# SL-CA025-ESP07S_V1_0.net
KiCad netlist of a schematic drawn in Altium Designer
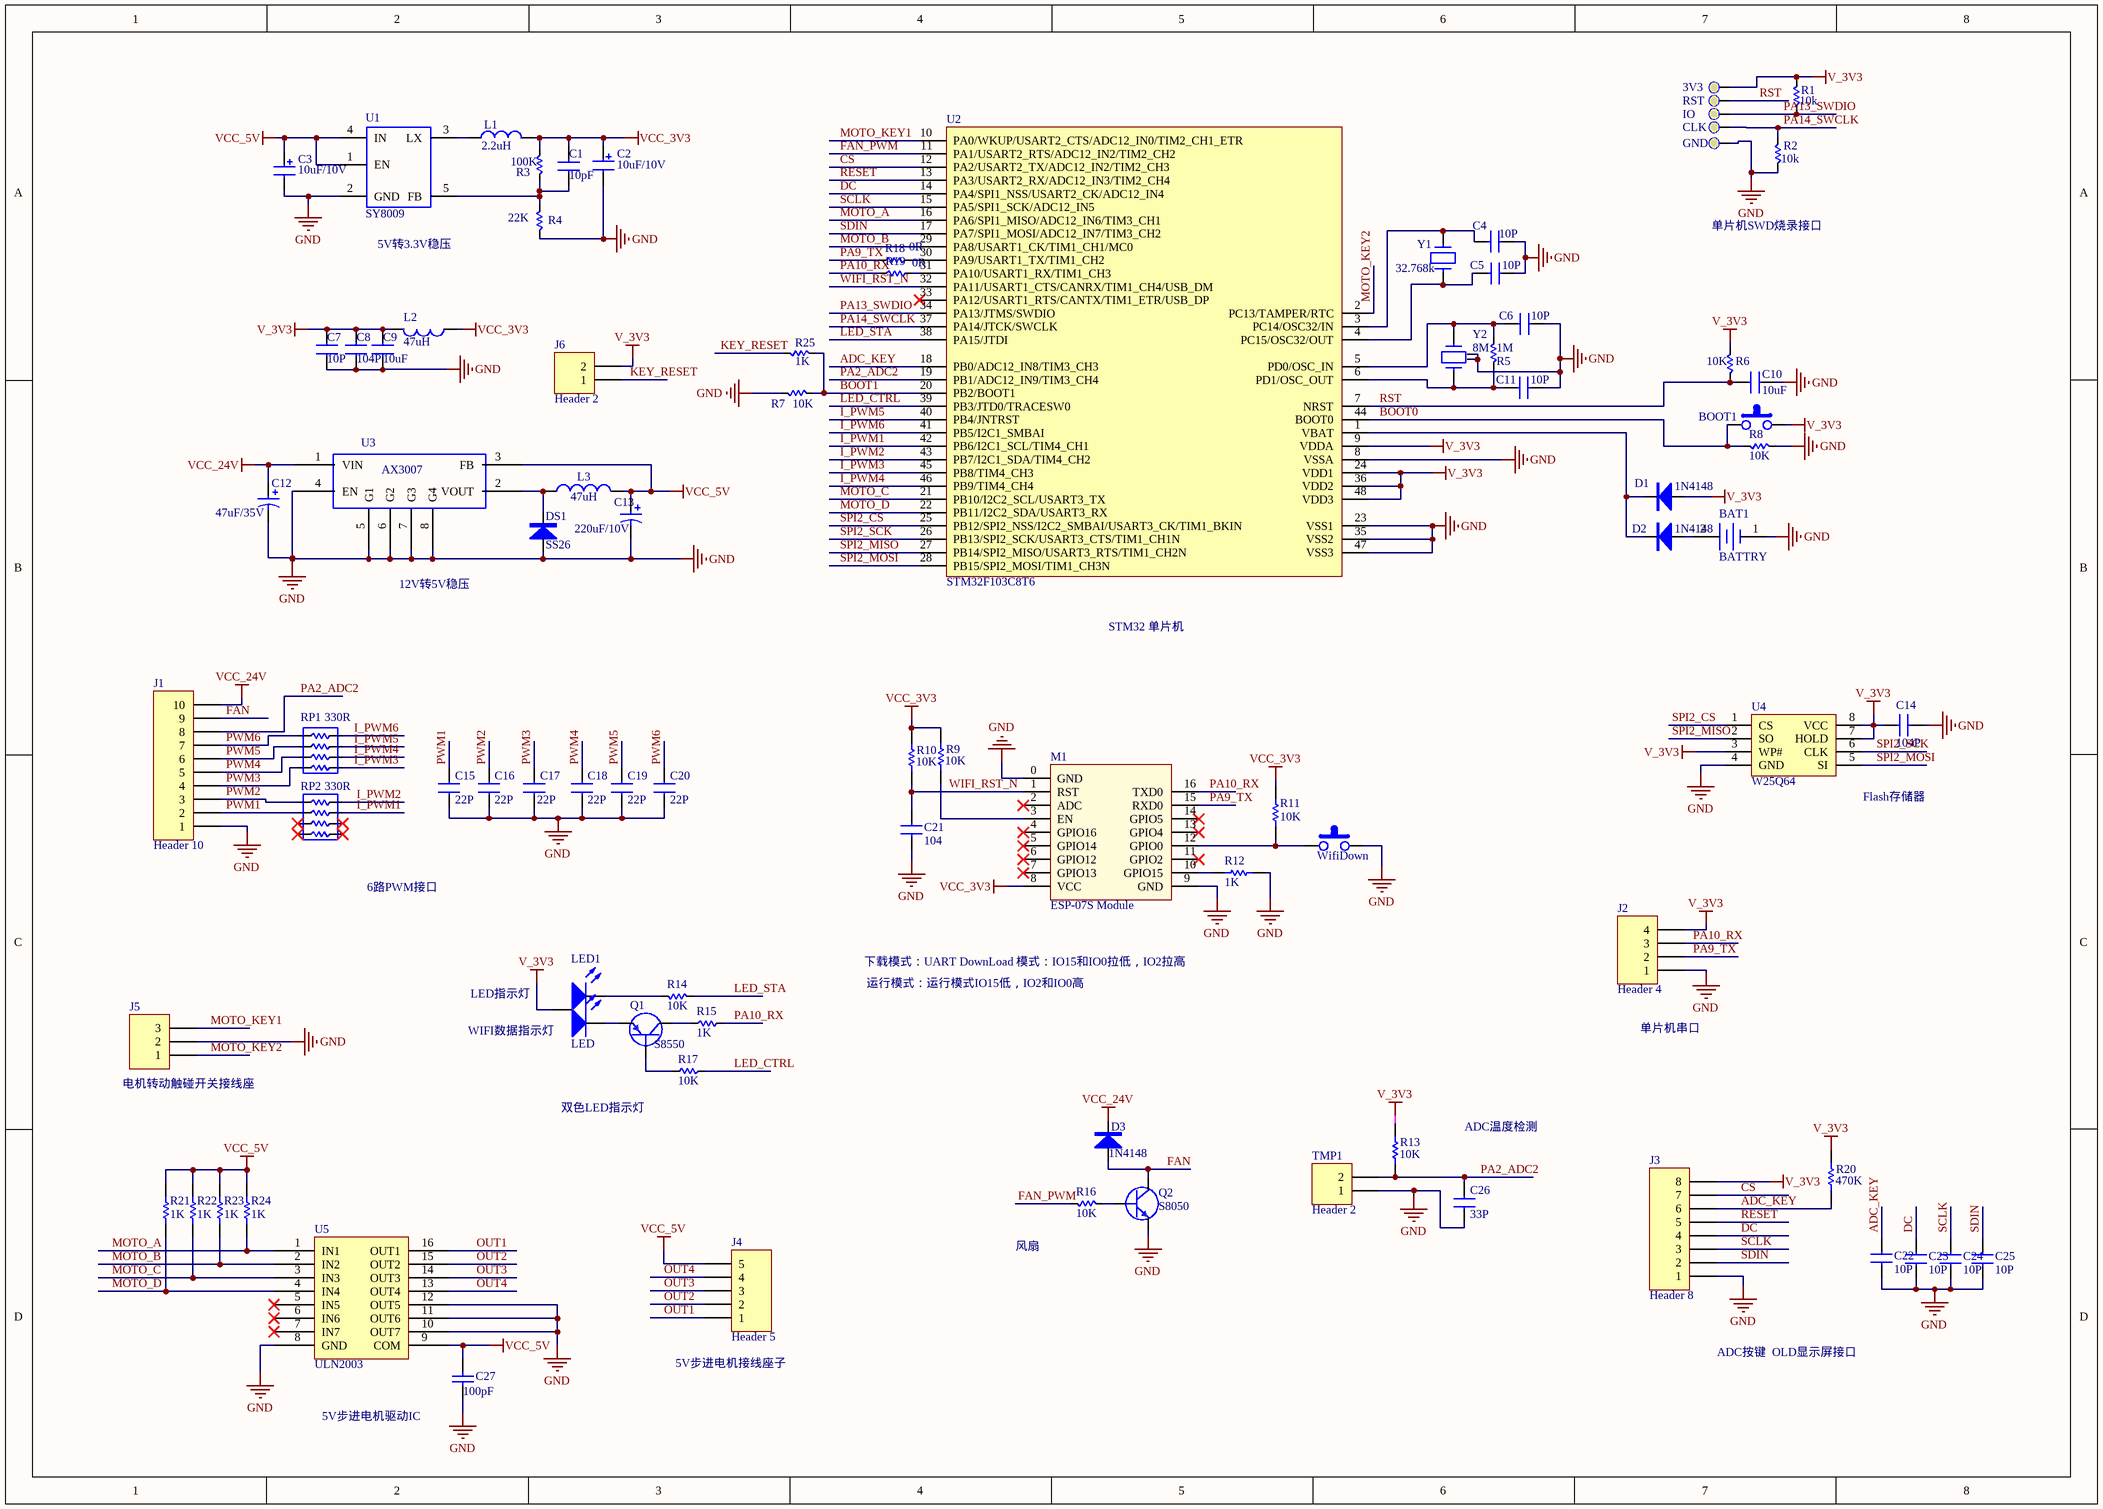
[diagram p0: SL-CA025-ESP07S_V1.0.SchDoc]

(export (version "E")
  (design (tool "Eeschema 10.0.6"))
  (components
    (comp (ref "3V3") (value "TP") (footprint "TP1") (libsource (lib "LED调光控制板") (part "TP1")))
    (comp (ref "BAT1") (value "BATTRY") (footprint "BAT_1220") (libsource (lib "LED调光控制板") (part "BATTRY")))
    (comp (ref "BOOT1") (value "SW") (footprint "SW_3X6") (libsource (lib "") (part "Button2_1")))
    (comp (ref "C1")
      (value "10pF")
      (footprint "C0603")
      (description "Capacitor")
      (libsource (lib "LED调光控制板") (part "CAP"))
    )
    (comp (ref "C2") (value "10uF/10V") (footprint "C0805") (libsource (lib "LED调光控制板") (part "CAP+")))
    (comp (ref "C3") (value "10uF/10V") (footprint "C0805") (libsource (lib "LED调光控制板") (part "CAP+")))
    (comp (ref "C4")
      (value "10P")
      (footprint "C0603")
      (description "Capacitor")
      (libsource (lib "LED调光控制板") (part "CAP"))
    )
    (comp (ref "C5")
      (value "10P")
      (footprint "C0603")
      (description "Capacitor")
      (libsource (lib "LED调光控制板") (part "CAP"))
    )
    (comp (ref "C6")
      (value "10P")
      (footprint "C0603")
      (description "Capacitor")
      (libsource (lib "LED调光控制板") (part "CAP"))
    )
    (comp (ref "C7")
      (value "10P")
      (footprint "C0603")
      (description "Capacitor")
      (libsource (lib "LED调光控制板") (part "CAP"))
    )
    (comp (ref "C8")
      (value "104P")
      (footprint "C0603")
      (description "Capacitor")
      (libsource (lib "LED调光控制板") (part "CAP"))
    )
    (comp (ref "C9")
      (value "10uF")
      (footprint "C0805")
      (description "Capacitor")
      (libsource (lib "LED调光控制板") (part "CAP"))
    )
    (comp (ref "C10")
      (value "10uF")
      (footprint "C0805")
      (description "Capacitor")
      (libsource (lib "LED调光控制板") (part "CAP"))
    )
    (comp (ref "C11")
      (value "10P")
      (footprint "C0603")
      (description "Capacitor")
      (libsource (lib "LED调光控制板") (part "CAP"))
    )
    (comp (ref "C12")
      (value "47uF/35V")
      (footprint "C_SMT63(5.9*6.6mm)")
      (description "Bi-Polar Capacitor")
      (libsource (lib "模拟器件") (part "CAP2"))
    )
    (comp (ref "C13")
      (value "220uF/10V")
      (footprint "C_SMT63(5.9*6.6mm)")
      (description "Bi-Polar Capacitor")
      (libsource (lib "模拟器件") (part "CAP2"))
    )
    (comp (ref "C14")
      (value "104P")
      (footprint "C0603")
      (description "Capacitor")
      (libsource (lib "LED调光控制板") (part "CAP"))
    )
    (comp (ref "C15")
      (value "22P")
      (footprint "C0603")
      (description "Capacitor")
      (libsource (lib "LED调光控制板") (part "CAP"))
    )
    (comp (ref "C16")
      (value "22P")
      (footprint "C0603")
      (description "Capacitor")
      (libsource (lib "LED调光控制板") (part "CAP"))
    )
    (comp (ref "C17")
      (value "22P")
      (footprint "C0603")
      (description "Capacitor")
      (libsource (lib "LED调光控制板") (part "CAP"))
    )
    (comp (ref "C18")
      (value "22P")
      (footprint "C0603")
      (description "Capacitor")
      (libsource (lib "LED调光控制板") (part "CAP"))
    )
    (comp (ref "C19")
      (value "22P")
      (footprint "C0603")
      (description "Capacitor")
      (libsource (lib "LED调光控制板") (part "CAP"))
    )
    (comp (ref "C20")
      (value "22P")
      (footprint "C0603")
      (description "Capacitor")
      (libsource (lib "LED调光控制板") (part "CAP"))
    )
    (comp (ref "C21")
      (value "104")
      (footprint "C0603")
      (description "Capacitor")
      (libsource (lib "LED调光控制板") (part "CAP"))
    )
    (comp (ref "C22")
      (value "10P")
      (footprint "C0603")
      (description "Capacitor")
      (libsource (lib "LED调光控制板") (part "CAP"))
    )
    (comp (ref "C23")
      (value "10P")
      (footprint "C0603")
      (description "Capacitor")
      (libsource (lib "LED调光控制板") (part "CAP"))
    )
    (comp (ref "C24")
      (value "10P")
      (footprint "C0603")
      (description "Capacitor")
      (libsource (lib "LED调光控制板") (part "CAP"))
    )
    (comp (ref "C25")
      (value "10P")
      (footprint "C0603")
      (description "Capacitor")
      (libsource (lib "LED调光控制板") (part "CAP"))
    )
    (comp (ref "C26")
      (value "33P")
      (footprint "C0603")
      (description "Capacitor")
      (libsource (lib "LED调光控制板") (part "CAP"))
    )
    (comp (ref "C27")
      (value "100pF")
      (footprint "C0603")
      (description "Capacitor")
      (fields (field (name "Comment") "Cap") (field (name "PUBLISHER") "Altium Limited"))
      (libsource (lib "Miscellaneous Devices") (part "Cap"))
    )
    (comp (ref "CLK") (value "TP") (footprint "TP1") (libsource (lib "LED调光控制板") (part "TP1")))
    (comp (ref "D1")
      (value "1N4148")
      (footprint "D0805")
      (description "DIODE")
      (libsource (lib "") (part "DIODE_2"))
    )
    (comp (ref "D2")
      (value "1N4148")
      (footprint "D0805")
      (description "DIODE")
      (libsource (lib "") (part "DIODE_1"))
    )
    (comp (ref "D3")
      (value "1N4148")
      (footprint "D0805")
      (description "DIODE")
      (libsource (lib "*") (part "DIODE"))
    )
    (comp (ref "DS1")
      (value "SS26")
      (footprint "SMA")
      (description "DIODE")
      (libsource (lib "") (part "DIODE_3"))
    )
    (comp (ref "GND") (value "TP") (footprint "TP1") (libsource (lib "LED调光控制板") (part "TP1")))
    (comp (ref "IO") (value "TP") (footprint "TP1") (libsource (lib "LED调光控制板") (part "TP1")))
    (comp (ref "J1")
      (value "Header 10")
      (footprint "CON10_1.5mm")
      (description "Header, 10-Pin, Right Angle")
      (fields (field (name "PUBLISHER") "Altium Limited"))
      (libsource (lib "Miscellaneous Connectors") (part "Header 10H"))
    )
    (comp (ref "J2")
      (value "Header 4")
      (footprint "SIP4A")
      (description "Header, 4-Pin")
      (fields (field (name "PUBLISHER") "Altium Limited"))
      (libsource (lib "Miscellaneous Connectors") (part "Header 4"))
    )
    (comp (ref "J3")
      (value "Header 8")
      (footprint "con8_1.5mm")
      (description "Header, 8-Pin")
      (fields (field (name "PUBLISHER") "Altium Limited"))
      (libsource (lib "Miscellaneous Connectors") (part "Header 8"))
    )
    (comp (ref "J4")
      (value "Header 5")
      (footprint "con5_1.5mm")
      (description "Header, 5-Pin")
      (fields (field (name "PUBLISHER") "Altium Limited"))
      (libsource (lib "Miscellaneous Connectors") (part "Header 5"))
    )
    (comp (ref "J5")
      (value "Header 3")
      (footprint "CON3_1.5mm")
      (description "Header, 3-Pin")
      (fields (field (name "PUBLISHER") "Altium Limited"))
      (libsource (lib "Miscellaneous Connectors") (part "Header 3"))
    )
    (comp (ref "J6")
      (value "Header 2")
      (footprint "CON2_1.5mm")
      (description "Header, 2-Pin")
      (fields (field (name "PUBLISHER") "Altium Limited"))
      (libsource (lib "Miscellaneous Connectors") (part "Header 2"))
    )
    (comp (ref "L1") (value "2.2uH") (footprint "L2520") (libsource (lib "LED调光控制板") (part "L")))
    (comp (ref "L2") (value "47uH") (footprint "L0805") (libsource (lib "LED调光控制板") (part "L")))
    (comp (ref "L3")
      (value "47uH")
      (footprint "L_SMRH_7.3x7.3")
      (description "Inductor")
      (libsource (lib "*") (part "INDUCTOR"))
    )
    (comp (ref "LED1")
      (value "LED")
      (footprint "LED_2K")
      (description "共阳极双色LED")
      (libsource (lib "MyShcLib") (part "LED_2K"))
    )
    (comp (ref "M1")
      (value "ESP-07S Module")
      (footprint "ESP-07S Module")
      (libsource (lib "ESP-07S Module") (part "ESP-07S Module"))
    )
    (comp (ref "Q1") (value "S8550") (footprint "SOT23-3") (libsource (lib "MyShcLib") (part "PNP")))
    (comp (ref "Q2") (value "S8050") (footprint "SOT23-3") (libsource (lib "LED调光控制板") (part "PNP2")))
    (comp (ref "R1") (value "10k") (footprint "R0603") (libsource (lib "LED调光控制板") (part "RES")))
    (comp (ref "R2") (value "10k") (footprint "R0603") (libsource (lib "LED调光控制板") (part "RES")))
    (comp (ref "R3") (value "100K") (footprint "R0603") (libsource (lib "LED调光控制板") (part "RES")))
    (comp (ref "R4") (value "22K") (footprint "R0603") (libsource (lib "LED调光控制板") (part "RES")))
    (comp (ref "R5") (value "1M") (footprint "R0603") (libsource (lib "LED调光控制板") (part "RES")))
    (comp (ref "R6") (value "10K") (footprint "R0603") (libsource (lib "LED调光控制板") (part "RES")))
    (comp (ref "R7") (value "10K") (footprint "R0603") (libsource (lib "LED调光控制板") (part "RES")))
    (comp (ref "R8") (value "10K") (footprint "R0603") (libsource (lib "LED调光控制板") (part "RES")))
    (comp (ref "R9")
      (value "10K")
      (footprint "R0603")
      (description "Resistor")
      (fields (field (name "PUBLISHER") "Altium Limited"))
      (libsource (lib "Miscellaneous Devices") (part "Res1"))
    )
    (comp (ref "R10")
      (value "10K")
      (footprint "R0603")
      (description "Resistor")
      (fields (field (name "PUBLISHER") "Altium Limited"))
      (libsource (lib "Miscellaneous Devices") (part "Res1"))
    )
    (comp (ref "R11")
      (value "10K")
      (footprint "R0603")
      (description "Resistor")
      (fields (field (name "PUBLISHER") "Altium Limited"))
      (libsource (lib "Miscellaneous Devices") (part "Res1"))
    )
    (comp (ref "R12")
      (value "1K")
      (footprint "R0603")
      (description "Resistor")
      (fields (field (name "PUBLISHER") "Altium Limited"))
      (libsource (lib "Miscellaneous Devices") (part "Res1"))
    )
    (comp (ref "R13")
      (value "10K")
      (footprint "R0603")
      (description "Resistor")
      (fields (field (name "PUBLISHER") "Altium Limited"))
      (libsource (lib "Miscellaneous Devices") (part "Res1"))
    )
    (comp (ref "R14") (value "10K") (footprint "R0603") (libsource (lib "LED调光控制板") (part "RES")))
    (comp (ref "R15") (value "1K") (footprint "R0603") (libsource (lib "LED调光控制板") (part "RES")))
    (comp (ref "R16") (value "10K") (footprint "R0603") (libsource (lib "LED调光控制板") (part "RES")))
    (comp (ref "R17") (value "10K") (footprint "R0603") (libsource (lib "LED调光控制板") (part "RES")))
    (comp (ref "R18") (value "0R") (footprint "R0603") (libsource (lib "LED调光控制板") (part "RES")))
    (comp (ref "R19") (value "0R") (footprint "R0603") (libsource (lib "LED调光控制板") (part "RES")))
    (comp (ref "R20")
      (value "470K")
      (footprint "R0603")
      (description "Resistor")
      (fields (field (name "PUBLISHER") "Altium Limited"))
      (libsource (lib "Miscellaneous Devices") (part "Res1"))
    )
    (comp (ref "R21")
      (value "1K")
      (footprint "R0603")
      (description "Resistor")
      (fields (field (name "Comment") "Res1") (field (name "PUBLISHER") "Altium Limited"))
      (libsource (lib "Miscellaneous Devices") (part "Res1"))
    )
    (comp (ref "R22")
      (value "1K")
      (footprint "R0603")
      (description "Resistor")
      (fields (field (name "Comment") "Res1") (field (name "PUBLISHER") "Altium Limited"))
      (libsource (lib "Miscellaneous Devices") (part "Res1"))
    )
    (comp (ref "R23")
      (value "1K")
      (footprint "R0603")
      (description "Resistor")
      (fields (field (name "Comment") "Res1") (field (name "PUBLISHER") "Altium Limited"))
      (libsource (lib "Miscellaneous Devices") (part "Res1"))
    )
    (comp (ref "R24")
      (value "1K")
      (footprint "R0603")
      (description "Resistor")
      (fields (field (name "Comment") "Res1") (field (name "PUBLISHER") "Altium Limited"))
      (libsource (lib "Miscellaneous Devices") (part "Res1"))
    )
    (comp (ref "R25") (value "1K") (footprint "R0603") (libsource (lib "LED调光控制板") (part "RES")))
    (comp (ref "RP1") (value "330R") (footprint "RP4_0603") (libsource (lib "LED调光控制板") (part "RES_PACK4")))
    (comp (ref "RP2") (value "330R") (footprint "RP4_0603") (libsource (lib "LED调光控制板") (part "RES_PACK4")))
    (comp (ref "RST") (value "TP") (footprint "TP1") (libsource (lib "LED调光控制板") (part "TP1")))
    (comp (ref "TMP1")
      (value "Header 2")
      (footprint "CON2_1.5mm")
      (description "Header, 2-Pin")
      (fields (field (name "PUBLISHER") "Altium Limited"))
      (libsource (lib "Miscellaneous Connectors") (part "Header 2"))
    )
    (comp (ref "U1") (value "SY8009") (footprint "SOT23-5") (libsource (lib "LED调光控制板") (part "SY8009")))
    (comp (ref "U2")
      (value "STM32F103C8T6")
      (footprint "LQFP48_9.2x9.2mm")
      (libsource (lib "LED调光控制板") (part "STM32F103C8T6"))
    )
    (comp (ref "U3") (value "AX3007") (footprint "SOP8_N") (libsource (lib "LED调光控制板") (part "AX3007")))
    (comp (ref "U4") (value "W25Q64") (footprint "SOIC8") (libsource (lib "LED调光控制板") (part "W25Q64")))
    (comp (ref "U5")
      (value "ULN2003")
      (footprint "SOP16")
      (description "电机驱动IC")
      (libsource (lib "ULN2003") (part "ULN2003"))
    )
    (comp (ref "WifiDown") (value "SW") (footprint "SW_3X6") (libsource (lib "LED调光控制板") (part "Button2")))
    (comp (ref "Y1") (value "32.768k") (footprint "XALT_3215") (libsource (lib "LED调光控制板") (part "CRYSTAL")))
    (comp (ref "Y2") (value "8M") (footprint "XALT_5032_4P") (libsource (lib "LED调光控制板") (part "Crystal_4p")))
  )
  (nets
    (net (code "1") (name "/ADC_KEY") (class "Default")
      (node (ref "C22") (pin "2") (pinfunction "2_2") (pintype "passive"))
      (node (ref "J3") (pin "6") (pinfunction "6_6") (pintype "passive"))
      (node (ref "R20") (pin "2") (pinfunction "2_2") (pintype "passive"))
      (node (ref "U2") (pin "18") (pinfunction "PB0/ADC12_IN8/TIM3_CH3_18") (pintype "passive"))
    )
    (net (code "2") (name "/BOOT0") (class "Default")
      (node (ref "BOOT1") (pin "1") (pinfunction "1_1") (pintype "passive"))
      (node (ref "R8") (pin "1") (pintype "passive"))
      (node (ref "U2") (pin "44") (pinfunction "BOOT0_44") (pintype "passive"))
    )
    (net (code "3") (name "/BOOT1") (class "Default")
      (node (ref "R25") (pin "1") (pintype "passive"))
      (node (ref "R7") (pin "1") (pintype "passive"))
      (node (ref "U2") (pin "20") (pinfunction "PB2/BOOT1_20") (pintype "passive"))
    )
    (net (code "4") (name "/CS") (class "Default")
      (node (ref "J3") (pin "7") (pinfunction "7_7") (pintype "passive"))
      (node (ref "U2") (pin "12") (pinfunction "PA2/USART2_TX/ADC12_IN2/TIM2_CH3_12") (pintype "passive"))
    )
    (net (code "5") (name "/DC") (class "Default")
      (node (ref "C23") (pin "2") (pinfunction "2_2") (pintype "passive"))
      (node (ref "J3") (pin "4") (pinfunction "4_4") (pintype "passive"))
      (node (ref "U2") (pin "14") (pinfunction "PA4/SPI1_NSS/USART2_CK/ADC12_IN4_14") (pintype "passive"))
    )
    (net (code "6") (name "/FAN") (class "Default")
      (node (ref "D3") (pin "1") (pinfunction "1_1") (pintype "passive"))
      (node (ref "J1") (pin "9") (pinfunction "9_9") (pintype "passive"))
      (node (ref "Q2") (pin "3") (pinfunction "E_3") (pintype "passive"))
    )
    (net (code "7") (name "/FAN_PWM") (class "Default")
      (node (ref "R16") (pin "1") (pintype "passive"))
      (node (ref "U2") (pin "11") (pinfunction "PA1/USART2_RTS/ADC12_IN2/TIM2_CH2_11") (pintype "passive"))
    )
    (net (code "8") (name "/I_PWM1") (class "Default")
      (node (ref "RP2") (pin "6") (pintype "passive"))
      (node (ref "U2") (pin "42") (pinfunction "PB6/I2C1_SCL/TIM4_CH1_42") (pintype "passive"))
    )
    (net (code "9") (name "/I_PWM2") (class "Default")
      (node (ref "RP2") (pin "5") (pintype "passive"))
      (node (ref "U2") (pin "43") (pinfunction "PB7/I2C1_SDA/TIM4_CH2_43") (pintype "passive"))
    )
    (net (code "10") (name "/I_PWM3") (class "Default")
      (node (ref "RP1") (pin "8") (pintype "passive"))
      (node (ref "U2") (pin "45") (pinfunction "PB8/TIM4_CH3_45") (pintype "passive"))
    )
    (net (code "11") (name "/I_PWM4") (class "Default")
      (node (ref "RP1") (pin "7") (pintype "passive"))
      (node (ref "U2") (pin "46") (pinfunction "PB9/TIM4_CH4_46") (pintype "passive"))
    )
    (net (code "12") (name "/I_PWM5") (class "Default")
      (node (ref "RP1") (pin "6") (pintype "passive"))
      (node (ref "U2") (pin "40") (pinfunction "PB4/JNTRST_40") (pintype "passive"))
    )
    (net (code "13") (name "/I_PWM6") (class "Default")
      (node (ref "RP1") (pin "5") (pintype "passive"))
      (node (ref "U2") (pin "41") (pinfunction "PB5/I2C1_SMBAI_41") (pintype "passive"))
    )
    (net (code "14") (name "/KEY_RESET") (class "Default")
      (node (ref "J6") (pin "1") (pinfunction "1_1") (pintype "passive"))
      (node (ref "R25") (pin "2") (pintype "passive"))
    )
    (net (code "15") (name "/LED_CTRL") (class "Default")
      (node (ref "R17") (pin "2") (pintype "passive"))
      (node (ref "U2") (pin "39") (pinfunction "PB3/JTD0/TRACESW0_39") (pintype "passive"))
    )
    (net (code "16") (name "/LED_STA") (class "Default")
      (node (ref "R14") (pin "1") (pintype "passive"))
      (node (ref "U2") (pin "38") (pinfunction "PA15/JTDI_38") (pintype "passive"))
    )
    (net (code "17") (name "/MOTO_A") (class "Default")
      (node (ref "R24") (pin "1") (pinfunction "1_1") (pintype "passive"))
      (node (ref "U2") (pin "16") (pinfunction "PA6/SPI1_MISO/ADC12_IN6/TIM3_CH1_16") (pintype "passive"))
      (node (ref "U5") (pin "1") (pinfunction "IN1_1") (pintype "passive"))
    )
    (net (code "18") (name "/MOTO_B") (class "Default")
      (node (ref "R23") (pin "1") (pinfunction "1_1") (pintype "passive"))
      (node (ref "U2") (pin "29") (pinfunction "PA8/USART1_CK/TIM1_CH1/MC0_29") (pintype "passive"))
      (node (ref "U5") (pin "2") (pinfunction "IN2_2") (pintype "passive"))
    )
    (net (code "19") (name "/MOTO_C") (class "Default")
      (node (ref "R22") (pin "1") (pinfunction "1_1") (pintype "passive"))
      (node (ref "U2") (pin "21") (pinfunction "PB10/I2C2_SCL/USART3_TX_21") (pintype "passive"))
      (node (ref "U5") (pin "3") (pinfunction "IN3_3") (pintype "passive"))
    )
    (net (code "20") (name "/MOTO_D") (class "Default")
      (node (ref "R21") (pin "1") (pinfunction "1_1") (pintype "passive"))
      (node (ref "U2") (pin "22") (pinfunction "PB11/I2C2_SDA/USART3_RX_22") (pintype "passive"))
      (node (ref "U5") (pin "4") (pinfunction "IN4_4") (pintype "passive"))
    )
    (net (code "21") (name "/MOTO_KEY1") (class "Default")
      (node (ref "J5") (pin "3") (pinfunction "3_3") (pintype "passive"))
      (node (ref "U2") (pin "10") (pinfunction "PA0/WKUP/USART2_CTS/ADC12_IN0/TIM2_CH1_ETR_10") (pintype "passive"))
    )
    (net (code "22") (name "/MOTO_KEY2") (class "Default")
      (node (ref "J5") (pin "1") (pinfunction "1_1") (pintype "passive"))
      (node (ref "U2") (pin "2") (pinfunction "PC13/TAMPER/RTC_2") (pintype "passive"))
    )
    (net (code "23") (name "/OUT1") (class "Default")
      (node (ref "J4") (pin "1") (pinfunction "1_1") (pintype "passive"))
      (node (ref "U5") (pin "16") (pinfunction "OUT1_16") (pintype "passive"))
    )
    (net (code "24") (name "/OUT2") (class "Default")
      (node (ref "J4") (pin "2") (pinfunction "2_2") (pintype "passive"))
      (node (ref "U5") (pin "15") (pinfunction "OUT2_15") (pintype "passive"))
    )
    (net (code "25") (name "/OUT3") (class "Default")
      (node (ref "J4") (pin "3") (pinfunction "3_3") (pintype "passive"))
      (node (ref "U5") (pin "14") (pinfunction "OUT3_14") (pintype "passive"))
    )
    (net (code "26") (name "/OUT4") (class "Default")
      (node (ref "J4") (pin "4") (pinfunction "4_4") (pintype "passive"))
      (node (ref "U5") (pin "13") (pinfunction "OUT4_13") (pintype "passive"))
    )
    (net (code "27") (name "/PA2_ADC2") (class "Default")
      (node (ref "C26") (pin "2") (pinfunction "2_2") (pintype "passive"))
      (node (ref "J1") (pin "8") (pinfunction "8_8") (pintype "passive"))
      (node (ref "R13") (pin "2") (pinfunction "2_2") (pintype "passive"))
      (node (ref "TMP1") (pin "2") (pinfunction "2_2") (pintype "passive"))
      (node (ref "U2") (pin "19") (pinfunction "PB1/ADC12_IN9/TIM3_CH4_19") (pintype "passive"))
    )
    (net (code "28") (name "/PA9_TX") (class "Default")
      (node (ref "J2") (pin "2") (pinfunction "2_2") (pintype "passive"))
      (node (ref "M1") (pin "15") (pinfunction "RXD0_15") (pintype "passive"))
      (node (ref "R18") (pin "1") (pintype "passive"))
    )
    (net (code "29") (name "/PA10_RX") (class "Default")
      (node (ref "J2") (pin "3") (pinfunction "3_3") (pintype "passive"))
      (node (ref "M1") (pin "16") (pinfunction "TXD0_16") (pintype "passive"))
      (node (ref "R15") (pin "1") (pintype "passive"))
      (node (ref "R19") (pin "1") (pintype "passive"))
    )
    (net (code "30") (name "/PA13_SWDIO") (class "Default")
      (node (ref "IO") (pin "1") (pinfunction "1_1") (pintype "passive"))
      (node (ref "R1") (pin "1") (pintype "passive"))
      (node (ref "U2") (pin "34") (pinfunction "PA13/JTMS/SWDIO_34") (pintype "passive"))
    )
    (net (code "31") (name "/PA14_SWCLK") (class "Default")
      (node (ref "CLK") (pin "1") (pinfunction "1_1") (pintype "passive"))
      (node (ref "R2") (pin "2") (pintype "passive"))
      (node (ref "U2") (pin "37") (pinfunction "PA14/JTCK/SWCLK_37") (pintype "passive"))
    )
    (net (code "32") (name "/PWM1") (class "Default")
      (node (ref "C15") (pin "2") (pinfunction "2_2") (pintype "passive"))
      (node (ref "J1") (pin "2") (pinfunction "2_2") (pintype "passive"))
      (node (ref "RP2") (pin "3") (pintype "passive"))
    )
    (net (code "33") (name "/PWM2") (class "Default")
      (node (ref "C16") (pin "2") (pinfunction "2_2") (pintype "passive"))
      (node (ref "J1") (pin "3") (pinfunction "3_3") (pintype "passive"))
      (node (ref "RP2") (pin "4") (pintype "passive"))
    )
    (net (code "34") (name "/PWM3") (class "Default")
      (node (ref "C17") (pin "2") (pinfunction "2_2") (pintype "passive"))
      (node (ref "J1") (pin "4") (pinfunction "4_4") (pintype "passive"))
      (node (ref "RP1") (pin "1") (pintype "passive"))
    )
    (net (code "35") (name "/PWM4") (class "Default")
      (node (ref "C18") (pin "2") (pinfunction "2_2") (pintype "passive"))
      (node (ref "J1") (pin "5") (pinfunction "5_5") (pintype "passive"))
      (node (ref "RP1") (pin "2") (pintype "passive"))
    )
    (net (code "36") (name "/PWM5") (class "Default")
      (node (ref "C19") (pin "2") (pinfunction "2_2") (pintype "passive"))
      (node (ref "J1") (pin "6") (pinfunction "6_6") (pintype "passive"))
      (node (ref "RP1") (pin "3") (pintype "passive"))
    )
    (net (code "37") (name "/PWM6") (class "Default")
      (node (ref "C20") (pin "2") (pinfunction "2_2") (pintype "passive"))
      (node (ref "J1") (pin "7") (pinfunction "7_7") (pintype "passive"))
      (node (ref "RP1") (pin "4") (pintype "passive"))
    )
    (net (code "38") (name "/RESET") (class "Default")
      (node (ref "J3") (pin "5") (pinfunction "5_5") (pintype "passive"))
      (node (ref "U2") (pin "13") (pinfunction "PA3/USART2_RX/ADC12_IN3/TIM2_CH4_13") (pintype "passive"))
    )
    (net (code "39") (name "/RST") (class "Default")
      (node (ref "C10") (pin "1") (pinfunction "1_1") (pintype "passive"))
      (node (ref "R6") (pin "1") (pintype "passive"))
      (node (ref "RST") (pin "1") (pinfunction "1_1") (pintype "passive"))
      (node (ref "U2") (pin "7") (pinfunction "NRST_7") (pintype "passive"))
    )
    (net (code "40") (name "/SCLK") (class "Default")
      (node (ref "C24") (pin "2") (pinfunction "2_2") (pintype "passive"))
      (node (ref "J3") (pin "3") (pinfunction "3_3") (pintype "passive"))
      (node (ref "U2") (pin "15") (pinfunction "PA5/SPI1_SCK/ADC12_IN5_15") (pintype "passive"))
    )
    (net (code "41") (name "/SDIN") (class "Default")
      (node (ref "C25") (pin "2") (pinfunction "2_2") (pintype "passive"))
      (node (ref "J3") (pin "2") (pinfunction "2_2") (pintype "passive"))
      (node (ref "U2") (pin "17") (pinfunction "PA7/SPI1_MOSI/ADC12_IN7/TIM3_CH2_17") (pintype "passive"))
    )
    (net (code "42") (name "/SPI2_CS") (class "Default")
      (node (ref "U2") (pin "25") (pinfunction "PB12/SPI2_NSS/I2C2_SMBAI/USART3_CK/TIM1_BKIN_25") (pintype "passive"))
      (node (ref "U4") (pin "1") (pinfunction "CS_1") (pintype "passive"))
    )
    (net (code "43") (name "/SPI2_MISO") (class "Default")
      (node (ref "U2") (pin "27") (pinfunction "PB14/SPI2_MISO/USART3_RTS/TIM1_CH2N_27") (pintype "passive"))
      (node (ref "U4") (pin "2") (pinfunction "SO_2") (pintype "passive"))
    )
    (net (code "44") (name "/SPI2_MOSI") (class "Default")
      (node (ref "U2") (pin "28") (pinfunction "PB15/SPI2_MOSI/TIM1_CH3N_28") (pintype "passive"))
      (node (ref "U4") (pin "5") (pinfunction "SI_5") (pintype "passive"))
    )
    (net (code "45") (name "/SPI2_SCK") (class "Default")
      (node (ref "U2") (pin "26") (pinfunction "PB13/SPI2_SCK/USART3_CTS/TIM1_CH1N_26") (pintype "passive"))
      (node (ref "U4") (pin "6") (pinfunction "CLK_6") (pintype "passive"))
    )
    (net (code "46") (name "/WIFI_RST_N") (class "Default")
      (node (ref "C21") (pin "1") (pinfunction "1_1") (pintype "passive"))
      (node (ref "M1") (pin "1") (pinfunction "RST_1") (pintype "passive"))
      (node (ref "R10") (pin "2") (pinfunction "2_2") (pintype "passive"))
      (node (ref "U2") (pin "32") (pinfunction "PA11/USART1_CTS/CANRX/TIM1_CH4/USB_DM_32") (pintype "passive"))
    )
    (net (code "47") (name "GND") (class "Default")
      (node (ref "BAT1") (pin "1") (pintype "passive"))
      (node (ref "C10") (pin "2") (pinfunction "2_2") (pintype "passive"))
      (node (ref "C11") (pin "2") (pinfunction "2_2") (pintype "passive"))
      (node (ref "C12") (pin "2") (pinfunction "2_2") (pintype "passive"))
      (node (ref "C13") (pin "2") (pinfunction "2_2") (pintype "passive"))
      (node (ref "C14") (pin "2") (pinfunction "2_2") (pintype "passive"))
      (node (ref "C15") (pin "1") (pinfunction "1_1") (pintype "passive"))
      (node (ref "C16") (pin "1") (pinfunction "1_1") (pintype "passive"))
      (node (ref "C17") (pin "1") (pinfunction "1_1") (pintype "passive"))
      (node (ref "C18") (pin "1") (pinfunction "1_1") (pintype "passive"))
      (node (ref "C19") (pin "1") (pinfunction "1_1") (pintype "passive"))
      (node (ref "C2") (pin "2") (pinfunction "2_2") (pintype "passive"))
      (node (ref "C20") (pin "1") (pinfunction "1_1") (pintype "passive"))
      (node (ref "C21") (pin "2") (pinfunction "2_2") (pintype "passive"))
      (node (ref "C22") (pin "1") (pinfunction "1_1") (pintype "passive"))
      (node (ref "C23") (pin "1") (pinfunction "1_1") (pintype "passive"))
      (node (ref "C24") (pin "1") (pinfunction "1_1") (pintype "passive"))
      (node (ref "C25") (pin "1") (pinfunction "1_1") (pintype "passive"))
      (node (ref "C26") (pin "1") (pinfunction "1_1") (pintype "passive"))
      (node (ref "C27") (pin "1") (pinfunction "1_1") (pintype "passive"))
      (node (ref "C3") (pin "2") (pinfunction "2_2") (pintype "passive"))
      (node (ref "C4") (pin "2") (pinfunction "2_2") (pintype "passive"))
      (node (ref "C5") (pin "2") (pinfunction "2_2") (pintype "passive"))
      (node (ref "C6") (pin "2") (pinfunction "2_2") (pintype "passive"))
      (node (ref "C7") (pin "2") (pinfunction "2_2") (pintype "passive"))
      (node (ref "C8") (pin "2") (pinfunction "2_2") (pintype "passive"))
      (node (ref "C9") (pin "2") (pinfunction "2_2") (pintype "passive"))
      (node (ref "DS1") (pin "1") (pinfunction "A_1") (pintype "passive"))
      (node (ref "GND") (pin "1") (pinfunction "1_1") (pintype "passive"))
      (node (ref "J1") (pin "1") (pinfunction "1_1") (pintype "passive"))
      (node (ref "J2") (pin "1") (pinfunction "1_1") (pintype "passive"))
      (node (ref "J3") (pin "1") (pinfunction "1_1") (pintype "passive"))
      (node (ref "J5") (pin "2") (pinfunction "2_2") (pintype "passive"))
      (node (ref "M1") (pin "0") (pinfunction "GND_0") (pintype "passive"))
      (node (ref "M1") (pin "9") (pinfunction "GND_9") (pintype "passive"))
      (node (ref "Q2") (pin "2") (pinfunction "E_2") (pintype "passive"))
      (node (ref "R12") (pin "2") (pinfunction "2_2") (pintype "passive"))
      (node (ref "R2") (pin "1") (pintype "passive"))
      (node (ref "R4") (pin "1") (pintype "passive"))
      (node (ref "R7") (pin "2") (pintype "passive"))
      (node (ref "R8") (pin "2") (pintype "passive"))
      (node (ref "TMP1") (pin "1") (pinfunction "1_1") (pintype "passive"))
      (node (ref "U1") (pin "2") (pinfunction "GND_2") (pintype "passive"))
      (node (ref "U2") (pin "23") (pinfunction "VSS1_23") (pintype "passive"))
      (node (ref "U2") (pin "35") (pinfunction "VSS2_35") (pintype "passive"))
      (node (ref "U2") (pin "47") (pinfunction "VSS3_47") (pintype "passive"))
      (node (ref "U2") (pin "8") (pinfunction "VSSA_8") (pintype "passive"))
      (node (ref "U3") (pin "4") (pinfunction "EN_4") (pintype "passive"))
      (node (ref "U3") (pin "5") (pinfunction "G1_5") (pintype "passive"))
      (node (ref "U3") (pin "6") (pinfunction "G2_6") (pintype "passive"))
      (node (ref "U3") (pin "7") (pinfunction "G3_7") (pintype "passive"))
      (node (ref "U3") (pin "8") (pinfunction "G4_8") (pintype "passive"))
      (node (ref "U4") (pin "4") (pinfunction "GND_4") (pintype "passive"))
      (node (ref "U5") (pin "10") (pinfunction "OUT7_10") (pintype "passive"))
      (node (ref "U5") (pin "11") (pinfunction "OUT6_11") (pintype "passive"))
      (node (ref "U5") (pin "12") (pinfunction "OUT5_12") (pintype "passive"))
      (node (ref "U5") (pin "8") (pinfunction "GND_8") (pintype "passive"))
      (node (ref "WifiDown") (pin "2") (pinfunction "2_2") (pintype "passive"))
      (node (ref "Y2") (pin "2") (pinfunction "GND_2") (pintype "passive"))
      (node (ref "Y2") (pin "4") (pinfunction "GND_4") (pintype "passive"))
    )
    (net (code "48") (name "Net-(D2-A)") (class "Default")
      (node (ref "BAT1") (pin "2") (pintype "passive"))
      (node (ref "D2") (pin "1") (pinfunction "A_1") (pintype "passive"))
    )
    (net (code "49") (name "Net-(D2-K)") (class "Default")
      (node (ref "D1") (pin "2") (pinfunction "2_2") (pintype "passive"))
      (node (ref "D2") (pin "2") (pinfunction "K_2") (pintype "passive"))
      (node (ref "U2") (pin "1") (pinfunction "VBAT_1") (pintype "passive"))
    )
    (net (code "50") (name "Net-(DS1-K)") (class "Default")
      (node (ref "DS1") (pin "2") (pinfunction "K_2") (pintype "passive"))
      (node (ref "L3") (pin "1") (pinfunction "1_1") (pintype "passive"))
      (node (ref "U3") (pin "2") (pinfunction "VOUT_2") (pintype "passive"))
    )
    (net (code "51") (name "Net-(LED1-PadK1)") (class "Default")
      (node (ref "LED1") (pin "K1") (pinfunction "K1_K1") (pintype "passive"))
      (node (ref "R14") (pin "2") (pintype "passive"))
    )
    (net (code "52") (name "Net-(M1-EN)") (class "Default")
      (node (ref "M1") (pin "3") (pinfunction "EN_3") (pintype "passive"))
      (node (ref "R9") (pin "2") (pinfunction "2_2") (pintype "passive"))
    )
    (net (code "53") (name "Net-(M1-GPIO0)") (class "Default")
      (node (ref "M1") (pin "12") (pinfunction "GPIO0_12") (pintype "passive"))
      (node (ref "R11") (pin "1") (pinfunction "1_1") (pintype "passive"))
      (node (ref "WifiDown") (pin "1") (pinfunction "1_1") (pintype "passive"))
    )
    (net (code "54") (name "Net-(M1-GPIO15)") (class "Default")
      (node (ref "M1") (pin "10") (pinfunction "GPIO15_10") (pintype "passive"))
      (node (ref "R12") (pin "1") (pinfunction "1_1") (pintype "passive"))
    )
    (net (code "55") (name "Net-(Q1-B)") (class "Default")
      (node (ref "Q1") (pin "1") (pinfunction "B_1") (pintype "passive"))
      (node (ref "R17") (pin "1") (pintype "passive"))
    )
    (net (code "56") (name "Net-(Q1-C)") (class "Default")
      (node (ref "Q1") (pin "3") (pinfunction "C_3") (pintype "passive"))
      (node (ref "R15") (pin "2") (pintype "passive"))
    )
    (net (code "57") (name "Net-(Q1-E)") (class "Default")
      (node (ref "LED1") (pin "K2") (pinfunction "K2_K2") (pintype "passive"))
      (node (ref "Q1") (pin "2") (pinfunction "E_2") (pintype "passive"))
    )
    (net (code "58") (name "Net-(Q2-B)") (class "Default")
      (node (ref "Q2") (pin "1") (pinfunction "B_1") (pintype "passive"))
      (node (ref "R16") (pin "2") (pintype "passive"))
    )
    (net (code "59") (name "Net-(U1-FB)") (class "Default")
      (node (ref "C1") (pin "2") (pinfunction "2_2") (pintype "passive"))
      (node (ref "R3") (pin "1") (pintype "passive"))
      (node (ref "R4") (pin "2") (pintype "passive"))
      (node (ref "U1") (pin "5") (pinfunction "FB_5") (pintype "passive"))
    )
    (net (code "60") (name "Net-(U1-LX)") (class "Default")
      (node (ref "L1") (pin "1") (pinfunction "1_1") (pintype "passive"))
      (node (ref "U1") (pin "3") (pinfunction "LX_3") (pintype "passive"))
    )
    (net (code "61") (name "Net-(U2-PA9{slash}USART1_TX{slash}TIM1_CH2)") (class "Default")
      (node (ref "R18") (pin "2") (pintype "passive"))
      (node (ref "U2") (pin "30") (pinfunction "PA9/USART1_TX/TIM1_CH2_30") (pintype "passive"))
    )
    (net (code "62") (name "Net-(U2-PA10{slash}USART1_RX{slash}TIM1_CH3)") (class "Default")
      (node (ref "R19") (pin "2") (pintype "passive"))
      (node (ref "U2") (pin "31") (pinfunction "PA10/USART1_RX/TIM1_CH3_31") (pintype "passive"))
    )
    (net (code "63") (name "Net-(U2-PC14{slash}OSC32{slash}IN)") (class "Default")
      (node (ref "C4") (pin "1") (pinfunction "1_1") (pintype "passive"))
      (node (ref "U2") (pin "3") (pinfunction "PC14/OSC32/IN_3") (pintype "passive"))
      (node (ref "Y1") (pin "2") (pintype "passive"))
    )
    (net (code "64") (name "Net-(U2-PC15{slash}OSC32{slash}OUT)") (class "Default")
      (node (ref "C5") (pin "1") (pinfunction "1_1") (pintype "passive"))
      (node (ref "U2") (pin "4") (pinfunction "PC15/OSC32/OUT_4") (pintype "passive"))
      (node (ref "Y1") (pin "1") (pintype "passive"))
    )
    (net (code "65") (name "Net-(U2-PD0{slash}OSC_IN)") (class "Default")
      (node (ref "C6") (pin "1") (pinfunction "1_1") (pintype "passive"))
      (node (ref "R5") (pin "2") (pintype "passive"))
      (node (ref "U2") (pin "5") (pinfunction "PD0/OSC_IN_5") (pintype "passive"))
      (node (ref "Y2") (pin "3") (pintype "passive"))
    )
    (net (code "66") (name "Net-(U2-PD1{slash}OSC_OUT)") (class "Default")
      (node (ref "C11") (pin "1") (pinfunction "1_1") (pintype "passive"))
      (node (ref "R5") (pin "1") (pintype "passive"))
      (node (ref "U2") (pin "6") (pinfunction "PD1/OSC_OUT_6") (pintype "passive"))
      (node (ref "Y2") (pin "1") (pintype "passive"))
    )
    (net (code "67") (name "VCC_3V3") (class "Default")
      (node (ref "C1") (pin "1") (pinfunction "1_1") (pintype "passive"))
      (node (ref "C2") (pin "1") (pinfunction "1_1") (pintype "passive"))
      (node (ref "L1") (pin "2") (pinfunction "2_2") (pintype "passive"))
      (node (ref "L2") (pin "1") (pinfunction "1_1") (pintype "passive"))
      (node (ref "M1") (pin "8") (pinfunction "VCC_8") (pintype "passive"))
      (node (ref "R10") (pin "1") (pinfunction "1_1") (pintype "passive"))
      (node (ref "R11") (pin "2") (pinfunction "2_2") (pintype "passive"))
      (node (ref "R3") (pin "2") (pintype "passive"))
      (node (ref "R9") (pin "1") (pinfunction "1_1") (pintype "passive"))
    )
    (net (code "68") (name "VCC_5V") (class "Default")
      (node (ref "C13") (pin "1") (pinfunction "1_1") (pintype "passive"))
      (node (ref "C27") (pin "2") (pinfunction "2_2") (pintype "passive"))
      (node (ref "C3") (pin "1") (pinfunction "1_1") (pintype "passive"))
      (node (ref "J4") (pin "5") (pinfunction "5_5") (pintype "passive"))
      (node (ref "L3") (pin "2") (pinfunction "2_2") (pintype "passive"))
      (node (ref "R21") (pin "2") (pinfunction "2_2") (pintype "passive"))
      (node (ref "R22") (pin "2") (pinfunction "2_2") (pintype "passive"))
      (node (ref "R23") (pin "2") (pinfunction "2_2") (pintype "passive"))
      (node (ref "R24") (pin "2") (pinfunction "2_2") (pintype "passive"))
      (node (ref "U1") (pin "1") (pinfunction "EN_1") (pintype "passive"))
      (node (ref "U1") (pin "4") (pinfunction "IN_4") (pintype "passive"))
      (node (ref "U3") (pin "3") (pinfunction "FB_3") (pintype "passive"))
      (node (ref "U5") (pin "9") (pinfunction "COM_9") (pintype "passive"))
    )
    (net (code "69") (name "VCC_24V") (class "Default")
      (node (ref "C12") (pin "1") (pinfunction "1_1") (pintype "passive"))
      (node (ref "D3") (pin "2") (pinfunction "2_2") (pintype "passive"))
      (node (ref "J1") (pin "10") (pinfunction "10_10") (pintype "passive"))
      (node (ref "U3") (pin "1") (pinfunction "VIN_1") (pintype "passive"))
    )
    (net (code "70") (name "V_3V3") (class "Default")
      (node (ref "3V3") (pin "1") (pinfunction "1_1") (pintype "passive"))
      (node (ref "BOOT1") (pin "2") (pinfunction "2_2") (pintype "passive"))
      (node (ref "C14") (pin "1") (pinfunction "1_1") (pintype "passive"))
      (node (ref "C7") (pin "1") (pinfunction "1_1") (pintype "passive"))
      (node (ref "C8") (pin "1") (pinfunction "1_1") (pintype "passive"))
      (node (ref "C9") (pin "1") (pinfunction "1_1") (pintype "passive"))
      (node (ref "D1") (pin "1") (pinfunction "1_1") (pintype "passive"))
      (node (ref "J2") (pin "4") (pinfunction "4_4") (pintype "passive"))
      (node (ref "J3") (pin "8") (pinfunction "8_8") (pintype "passive"))
      (node (ref "J6") (pin "2") (pinfunction "2_2") (pintype "passive"))
      (node (ref "L2") (pin "2") (pinfunction "2_2") (pintype "passive"))
      (node (ref "LED1") (pin "A") (pinfunction "A_A") (pintype "passive"))
      (node (ref "R1") (pin "2") (pintype "passive"))
      (node (ref "R13") (pin "1") (pinfunction "1_1") (pintype "passive"))
      (node (ref "R20") (pin "1") (pinfunction "1_1") (pintype "passive"))
      (node (ref "R6") (pin "2") (pintype "passive"))
      (node (ref "U2") (pin "24") (pinfunction "VDD1_24") (pintype "passive"))
      (node (ref "U2") (pin "36") (pinfunction "VDD2_36") (pintype "passive"))
      (node (ref "U2") (pin "48") (pinfunction "VDD3_48") (pintype "passive"))
      (node (ref "U2") (pin "9") (pinfunction "VDDA_9") (pintype "passive"))
      (node (ref "U4") (pin "3") (pinfunction "WP#_3") (pintype "passive"))
      (node (ref "U4") (pin "7") (pinfunction "HOLD_7") (pintype "passive"))
      (node (ref "U4") (pin "8") (pinfunction "VCC_8") (pintype "passive"))
    )
    (net (code "71") (name "unconnected-(M1-ADC-Pad2)") (class "Default")
      (node (ref "M1") (pin "2") (pinfunction "ADC_2") (pintype "passive+no_connect"))
    )
    (net (code "72") (name "unconnected-(M1-GPIO2-Pad11)") (class "Default")
      (node (ref "M1") (pin "11") (pinfunction "GPIO2_11") (pintype "passive+no_connect"))
    )
    (net (code "73") (name "unconnected-(M1-GPIO4-Pad13)") (class "Default")
      (node (ref "M1") (pin "13") (pinfunction "GPIO4_13") (pintype "passive+no_connect"))
    )
    (net (code "74") (name "unconnected-(M1-GPIO5-Pad14)") (class "Default")
      (node (ref "M1") (pin "14") (pinfunction "GPIO5_14") (pintype "passive+no_connect"))
    )
    (net (code "75") (name "unconnected-(M1-GPIO12-Pad6)") (class "Default")
      (node (ref "M1") (pin "6") (pinfunction "GPIO12_6") (pintype "passive+no_connect"))
    )
    (net (code "76") (name "unconnected-(M1-GPIO13-Pad7)") (class "Default")
      (node (ref "M1") (pin "7") (pinfunction "GPIO13_7") (pintype "passive+no_connect"))
    )
    (net (code "77") (name "unconnected-(M1-GPIO14-Pad5)") (class "Default")
      (node (ref "M1") (pin "5") (pinfunction "GPIO14_5") (pintype "passive+no_connect"))
    )
    (net (code "78") (name "unconnected-(M1-GPIO16-Pad4)") (class "Default")
      (node (ref "M1") (pin "4") (pinfunction "GPIO16_4") (pintype "passive+no_connect"))
    )
    (net (code "79") (name "unconnected-(RP2-Pad1)") (class "Default")
      (node (ref "RP2") (pin "1") (pintype "passive+no_connect"))
    )
    (net (code "80") (name "unconnected-(RP2-Pad2)") (class "Default")
      (node (ref "RP2") (pin "2") (pintype "passive+no_connect"))
    )
    (net (code "81") (name "unconnected-(RP2-Pad7)") (class "Default")
      (node (ref "RP2") (pin "7") (pintype "passive+no_connect"))
    )
    (net (code "82") (name "unconnected-(RP2-Pad8)") (class "Default")
      (node (ref "RP2") (pin "8") (pintype "passive+no_connect"))
    )
    (net (code "83") (name "unconnected-(U2-PA12{slash}USART1_RTS{slash}CANTX{slash}TIM1_ETR{slash}USB_DP-Pad33)") (class "Default")
      (node (ref "U2") (pin "33") (pinfunction "PA12/USART1_RTS/CANTX/TIM1_ETR/USB_DP_33") (pintype "passive+no_connect"))
    )
    (net (code "84") (name "unconnected-(U5-IN5-Pad5)") (class "Default")
      (node (ref "U5") (pin "5") (pinfunction "IN5_5") (pintype "passive+no_connect"))
    )
    (net (code "85") (name "unconnected-(U5-IN6-Pad6)") (class "Default")
      (node (ref "U5") (pin "6") (pinfunction "IN6_6") (pintype "passive+no_connect"))
    )
    (net (code "86") (name "unconnected-(U5-IN7-Pad7)") (class "Default")
      (node (ref "U5") (pin "7") (pinfunction "IN7_7") (pintype "passive+no_connect"))
    )
  )
)
